# 2XSFP_Arria10.net
KiCad netlist of a schematic drawn in Altium Designer
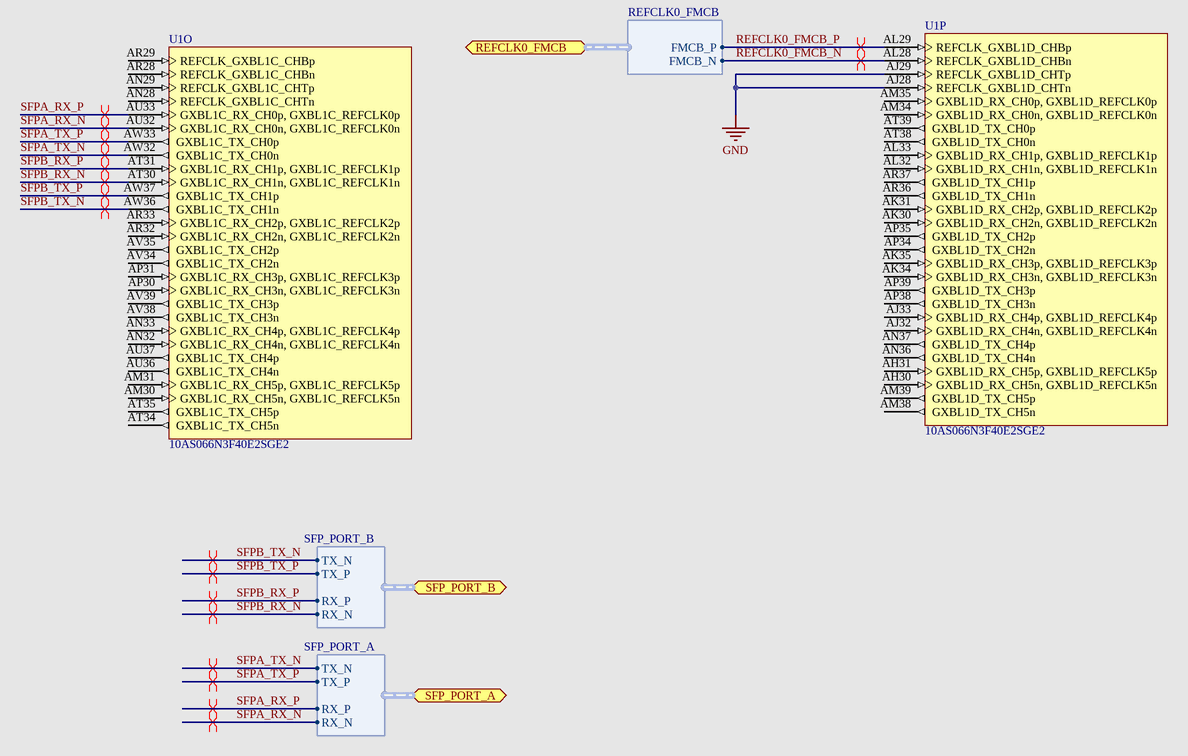
[diagram p0: 2XSFP_Arria10.SchDoc]

(export (version "E")
  (design (tool "Eeschema 10.0.6"))
  (components
    (comp (ref "U1")
      (value "10AS066N3F40E2SGE2")
      (footprint "ALTR-FBGA1517_A-350")
      (libsource (lib "Altium Content Vault") (part "ALTR-10AS066NF40-FBGA1517"))
    )
  )
  (nets
    (net (code "4") (name "/REFCLK0_FMCB_N") (class "Default")
      (node (ref "U1") (pin "AL28") (pinfunction "REFCLK_GXBL1D_CHBn_AL28") (pintype "input"))
    )
    (net (code "5") (name "/REFCLK0_FMCB_P") (class "Default")
      (node (ref "U1") (pin "AL29") (pinfunction "REFCLK_GXBL1D_CHBp_AL29") (pintype "input"))
    )
    (net (code "6") (name "/SFPA_RX_N") (class "Default")
      (node (ref "U1") (pin "AU32") (pinfunction "GXBL1C_RX_CH0n,_GXBL1C_REFCLK0n_AU32") (pintype "input"))
    )
    (net (code "7") (name "/SFPA_RX_P") (class "Default")
      (node (ref "U1") (pin "AU33") (pinfunction "GXBL1C_RX_CH0p,_GXBL1C_REFCLK0p_AU33") (pintype "input"))
    )
    (net (code "8") (name "/SFPA_TX_N") (class "Default")
      (node (ref "U1") (pin "AW32") (pinfunction "GXBL1C_TX_CH0n_AW32") (pintype "output"))
    )
    (net (code "9") (name "/SFPA_TX_P") (class "Default")
      (node (ref "U1") (pin "AW33") (pinfunction "GXBL1C_TX_CH0p_AW33") (pintype "output"))
    )
    (net (code "10") (name "/SFPB_RX_N") (class "Default")
      (node (ref "U1") (pin "AT30") (pinfunction "GXBL1C_RX_CH1n,_GXBL1C_REFCLK1n_AT30") (pintype "input"))
    )
    (net (code "11") (name "/SFPB_RX_P") (class "Default")
      (node (ref "U1") (pin "AT31") (pinfunction "GXBL1C_RX_CH1p,_GXBL1C_REFCLK1p_AT31") (pintype "input"))
    )
    (net (code "12") (name "/SFPB_TX_N") (class "Default")
      (node (ref "U1") (pin "AW36") (pinfunction "GXBL1C_TX_CH1n_AW36") (pintype "output"))
    )
    (net (code "13") (name "/SFPB_TX_P") (class "Default")
      (node (ref "U1") (pin "AW37") (pinfunction "GXBL1C_TX_CH1p_AW37") (pintype "output"))
    )
    (net (code "17") (name "GND") (class "Default")
      (node (ref "U1") (pin "AJ28") (pinfunction "REFCLK_GXBL1D_CHTn_AJ28") (pintype "input"))
      (node (ref "U1") (pin "AJ29") (pinfunction "REFCLK_GXBL1D_CHTp_AJ29") (pintype "input"))
    )
    (net (code "18") (name "unconnected-(U1O-GXBL1C_RX_CH2n,_GXBL1C_REFCLK2n-PadAR32)") (class "Default")
      (node (ref "U1") (pin "AR32") (pinfunction "GXBL1C_RX_CH2n,_GXBL1C_REFCLK2n_AR32") (pintype "input"))
    )
    (net (code "19") (name "unconnected-(U1O-GXBL1C_RX_CH2p,_GXBL1C_REFCLK2p-PadAR33)") (class "Default")
      (node (ref "U1") (pin "AR33") (pinfunction "GXBL1C_RX_CH2p,_GXBL1C_REFCLK2p_AR33") (pintype "input"))
    )
    (net (code "20") (name "unconnected-(U1O-GXBL1C_RX_CH3n,_GXBL1C_REFCLK3n-PadAP30)") (class "Default")
      (node (ref "U1") (pin "AP30") (pinfunction "GXBL1C_RX_CH3n,_GXBL1C_REFCLK3n_AP30") (pintype "input"))
    )
    (net (code "21") (name "unconnected-(U1O-GXBL1C_RX_CH3p,_GXBL1C_REFCLK3p-PadAP31)") (class "Default")
      (node (ref "U1") (pin "AP31") (pinfunction "GXBL1C_RX_CH3p,_GXBL1C_REFCLK3p_AP31") (pintype "input"))
    )
    (net (code "22") (name "unconnected-(U1O-GXBL1C_RX_CH4n,_GXBL1C_REFCLK4n-PadAN32)") (class "Default")
      (node (ref "U1") (pin "AN32") (pinfunction "GXBL1C_RX_CH4n,_GXBL1C_REFCLK4n_AN32") (pintype "input"))
    )
    (net (code "23") (name "unconnected-(U1O-GXBL1C_RX_CH4p,_GXBL1C_REFCLK4p-PadAN33)") (class "Default")
      (node (ref "U1") (pin "AN33") (pinfunction "GXBL1C_RX_CH4p,_GXBL1C_REFCLK4p_AN33") (pintype "input"))
    )
    (net (code "24") (name "unconnected-(U1O-GXBL1C_RX_CH5n,_GXBL1C_REFCLK5n-PadAM30)") (class "Default")
      (node (ref "U1") (pin "AM30") (pinfunction "GXBL1C_RX_CH5n,_GXBL1C_REFCLK5n_AM30") (pintype "input"))
    )
    (net (code "25") (name "unconnected-(U1O-GXBL1C_RX_CH5p,_GXBL1C_REFCLK5p-PadAM31)") (class "Default")
      (node (ref "U1") (pin "AM31") (pinfunction "GXBL1C_RX_CH5p,_GXBL1C_REFCLK5p_AM31") (pintype "input"))
    )
    (net (code "26") (name "unconnected-(U1O-GXBL1C_TX_CH2n-PadAV34)") (class "Default")
      (node (ref "U1") (pin "AV34") (pinfunction "GXBL1C_TX_CH2n_AV34") (pintype "output"))
    )
    (net (code "27") (name "unconnected-(U1O-GXBL1C_TX_CH2p-PadAV35)") (class "Default")
      (node (ref "U1") (pin "AV35") (pinfunction "GXBL1C_TX_CH2p_AV35") (pintype "output"))
    )
    (net (code "28") (name "unconnected-(U1O-GXBL1C_TX_CH3n-PadAV38)") (class "Default")
      (node (ref "U1") (pin "AV38") (pinfunction "GXBL1C_TX_CH3n_AV38") (pintype "output"))
    )
    (net (code "29") (name "unconnected-(U1O-GXBL1C_TX_CH3p-PadAV39)") (class "Default")
      (node (ref "U1") (pin "AV39") (pinfunction "GXBL1C_TX_CH3p_AV39") (pintype "output"))
    )
    (net (code "30") (name "unconnected-(U1O-GXBL1C_TX_CH4n-PadAU36)") (class "Default")
      (node (ref "U1") (pin "AU36") (pinfunction "GXBL1C_TX_CH4n_AU36") (pintype "output"))
    )
    (net (code "31") (name "unconnected-(U1O-GXBL1C_TX_CH4p-PadAU37)") (class "Default")
      (node (ref "U1") (pin "AU37") (pinfunction "GXBL1C_TX_CH4p_AU37") (pintype "output"))
    )
    (net (code "32") (name "unconnected-(U1O-GXBL1C_TX_CH5n-PadAT34)") (class "Default")
      (node (ref "U1") (pin "AT34") (pinfunction "GXBL1C_TX_CH5n_AT34") (pintype "output"))
    )
    (net (code "33") (name "unconnected-(U1O-GXBL1C_TX_CH5p-PadAT35)") (class "Default")
      (node (ref "U1") (pin "AT35") (pinfunction "GXBL1C_TX_CH5p_AT35") (pintype "output"))
    )
    (net (code "34") (name "unconnected-(U1O-REFCLK_GXBL1C_CHBn-PadAR28)") (class "Default")
      (node (ref "U1") (pin "AR28") (pinfunction "REFCLK_GXBL1C_CHBn_AR28") (pintype "input"))
    )
    (net (code "35") (name "unconnected-(U1O-REFCLK_GXBL1C_CHBp-PadAR29)") (class "Default")
      (node (ref "U1") (pin "AR29") (pinfunction "REFCLK_GXBL1C_CHBp_AR29") (pintype "input"))
    )
    (net (code "36") (name "unconnected-(U1O-REFCLK_GXBL1C_CHTn-PadAN28)") (class "Default")
      (node (ref "U1") (pin "AN28") (pinfunction "REFCLK_GXBL1C_CHTn_AN28") (pintype "input"))
    )
    (net (code "37") (name "unconnected-(U1O-REFCLK_GXBL1C_CHTp-PadAN29)") (class "Default")
      (node (ref "U1") (pin "AN29") (pinfunction "REFCLK_GXBL1C_CHTp_AN29") (pintype "input"))
    )
    (net (code "38") (name "unconnected-(U1P-GXBL1D_RX_CH0n,_GXBL1D_REFCLK0n-PadAM34)") (class "Default")
      (node (ref "U1") (pin "AM34") (pinfunction "GXBL1D_RX_CH0n,_GXBL1D_REFCLK0n_AM34") (pintype "input"))
    )
    (net (code "39") (name "unconnected-(U1P-GXBL1D_RX_CH0p,_GXBL1D_REFCLK0p-PadAM35)") (class "Default")
      (node (ref "U1") (pin "AM35") (pinfunction "GXBL1D_RX_CH0p,_GXBL1D_REFCLK0p_AM35") (pintype "input"))
    )
    (net (code "40") (name "unconnected-(U1P-GXBL1D_RX_CH1n,_GXBL1D_REFCLK1n-PadAL32)") (class "Default")
      (node (ref "U1") (pin "AL32") (pinfunction "GXBL1D_RX_CH1n,_GXBL1D_REFCLK1n_AL32") (pintype "input"))
    )
    (net (code "41") (name "unconnected-(U1P-GXBL1D_RX_CH1p,_GXBL1D_REFCLK1p-PadAL33)") (class "Default")
      (node (ref "U1") (pin "AL33") (pinfunction "GXBL1D_RX_CH1p,_GXBL1D_REFCLK1p_AL33") (pintype "input"))
    )
    (net (code "42") (name "unconnected-(U1P-GXBL1D_RX_CH2n,_GXBL1D_REFCLK2n-PadAK30)") (class "Default")
      (node (ref "U1") (pin "AK30") (pinfunction "GXBL1D_RX_CH2n,_GXBL1D_REFCLK2n_AK30") (pintype "input"))
    )
    (net (code "43") (name "unconnected-(U1P-GXBL1D_RX_CH2p,_GXBL1D_REFCLK2p-PadAK31)") (class "Default")
      (node (ref "U1") (pin "AK31") (pinfunction "GXBL1D_RX_CH2p,_GXBL1D_REFCLK2p_AK31") (pintype "input"))
    )
    (net (code "44") (name "unconnected-(U1P-GXBL1D_RX_CH3n,_GXBL1D_REFCLK3n-PadAK34)") (class "Default")
      (node (ref "U1") (pin "AK34") (pinfunction "GXBL1D_RX_CH3n,_GXBL1D_REFCLK3n_AK34") (pintype "input"))
    )
    (net (code "45") (name "unconnected-(U1P-GXBL1D_RX_CH3p,_GXBL1D_REFCLK3p-PadAK35)") (class "Default")
      (node (ref "U1") (pin "AK35") (pinfunction "GXBL1D_RX_CH3p,_GXBL1D_REFCLK3p_AK35") (pintype "input"))
    )
    (net (code "46") (name "unconnected-(U1P-GXBL1D_RX_CH4n,_GXBL1D_REFCLK4n-PadAJ32)") (class "Default")
      (node (ref "U1") (pin "AJ32") (pinfunction "GXBL1D_RX_CH4n,_GXBL1D_REFCLK4n_AJ32") (pintype "input"))
    )
    (net (code "47") (name "unconnected-(U1P-GXBL1D_RX_CH4p,_GXBL1D_REFCLK4p-PadAJ33)") (class "Default")
      (node (ref "U1") (pin "AJ33") (pinfunction "GXBL1D_RX_CH4p,_GXBL1D_REFCLK4p_AJ33") (pintype "input"))
    )
    (net (code "48") (name "unconnected-(U1P-GXBL1D_RX_CH5n,_GXBL1D_REFCLK5n-PadAH30)") (class "Default")
      (node (ref "U1") (pin "AH30") (pinfunction "GXBL1D_RX_CH5n,_GXBL1D_REFCLK5n_AH30") (pintype "input"))
    )
    (net (code "49") (name "unconnected-(U1P-GXBL1D_RX_CH5p,_GXBL1D_REFCLK5p-PadAH31)") (class "Default")
      (node (ref "U1") (pin "AH31") (pinfunction "GXBL1D_RX_CH5p,_GXBL1D_REFCLK5p_AH31") (pintype "input"))
    )
    (net (code "50") (name "unconnected-(U1P-GXBL1D_TX_CH0n-PadAT38)") (class "Default")
      (node (ref "U1") (pin "AT38") (pinfunction "GXBL1D_TX_CH0n_AT38") (pintype "output"))
    )
    (net (code "51") (name "unconnected-(U1P-GXBL1D_TX_CH0p-PadAT39)") (class "Default")
      (node (ref "U1") (pin "AT39") (pinfunction "GXBL1D_TX_CH0p_AT39") (pintype "output"))
    )
    (net (code "52") (name "unconnected-(U1P-GXBL1D_TX_CH1n-PadAR36)") (class "Default")
      (node (ref "U1") (pin "AR36") (pinfunction "GXBL1D_TX_CH1n_AR36") (pintype "output"))
    )
    (net (code "53") (name "unconnected-(U1P-GXBL1D_TX_CH1p-PadAR37)") (class "Default")
      (node (ref "U1") (pin "AR37") (pinfunction "GXBL1D_TX_CH1p_AR37") (pintype "output"))
    )
    (net (code "54") (name "unconnected-(U1P-GXBL1D_TX_CH2n-PadAP34)") (class "Default")
      (node (ref "U1") (pin "AP34") (pinfunction "GXBL1D_TX_CH2n_AP34") (pintype "output"))
    )
    (net (code "55") (name "unconnected-(U1P-GXBL1D_TX_CH2p-PadAP35)") (class "Default")
      (node (ref "U1") (pin "AP35") (pinfunction "GXBL1D_TX_CH2p_AP35") (pintype "output"))
    )
    (net (code "56") (name "unconnected-(U1P-GXBL1D_TX_CH3n-PadAP38)") (class "Default")
      (node (ref "U1") (pin "AP38") (pinfunction "GXBL1D_TX_CH3n_AP38") (pintype "output"))
    )
    (net (code "57") (name "unconnected-(U1P-GXBL1D_TX_CH3p-PadAP39)") (class "Default")
      (node (ref "U1") (pin "AP39") (pinfunction "GXBL1D_TX_CH3p_AP39") (pintype "output"))
    )
    (net (code "58") (name "unconnected-(U1P-GXBL1D_TX_CH4n-PadAN36)") (class "Default")
      (node (ref "U1") (pin "AN36") (pinfunction "GXBL1D_TX_CH4n_AN36") (pintype "output"))
    )
    (net (code "59") (name "unconnected-(U1P-GXBL1D_TX_CH4p-PadAN37)") (class "Default")
      (node (ref "U1") (pin "AN37") (pinfunction "GXBL1D_TX_CH4p_AN37") (pintype "output"))
    )
    (net (code "60") (name "unconnected-(U1P-GXBL1D_TX_CH5n-PadAM38)") (class "Default")
      (node (ref "U1") (pin "AM38") (pinfunction "GXBL1D_TX_CH5n_AM38") (pintype "output"))
    )
    (net (code "61") (name "unconnected-(U1P-GXBL1D_TX_CH5p-PadAM39)") (class "Default")
      (node (ref "U1") (pin "AM39") (pinfunction "GXBL1D_TX_CH5p_AM39") (pintype "output"))
    )
  )
)
